# CAS_SMPS_Sheet.net
KiCad netlist of a schematic drawn in Altium Designer
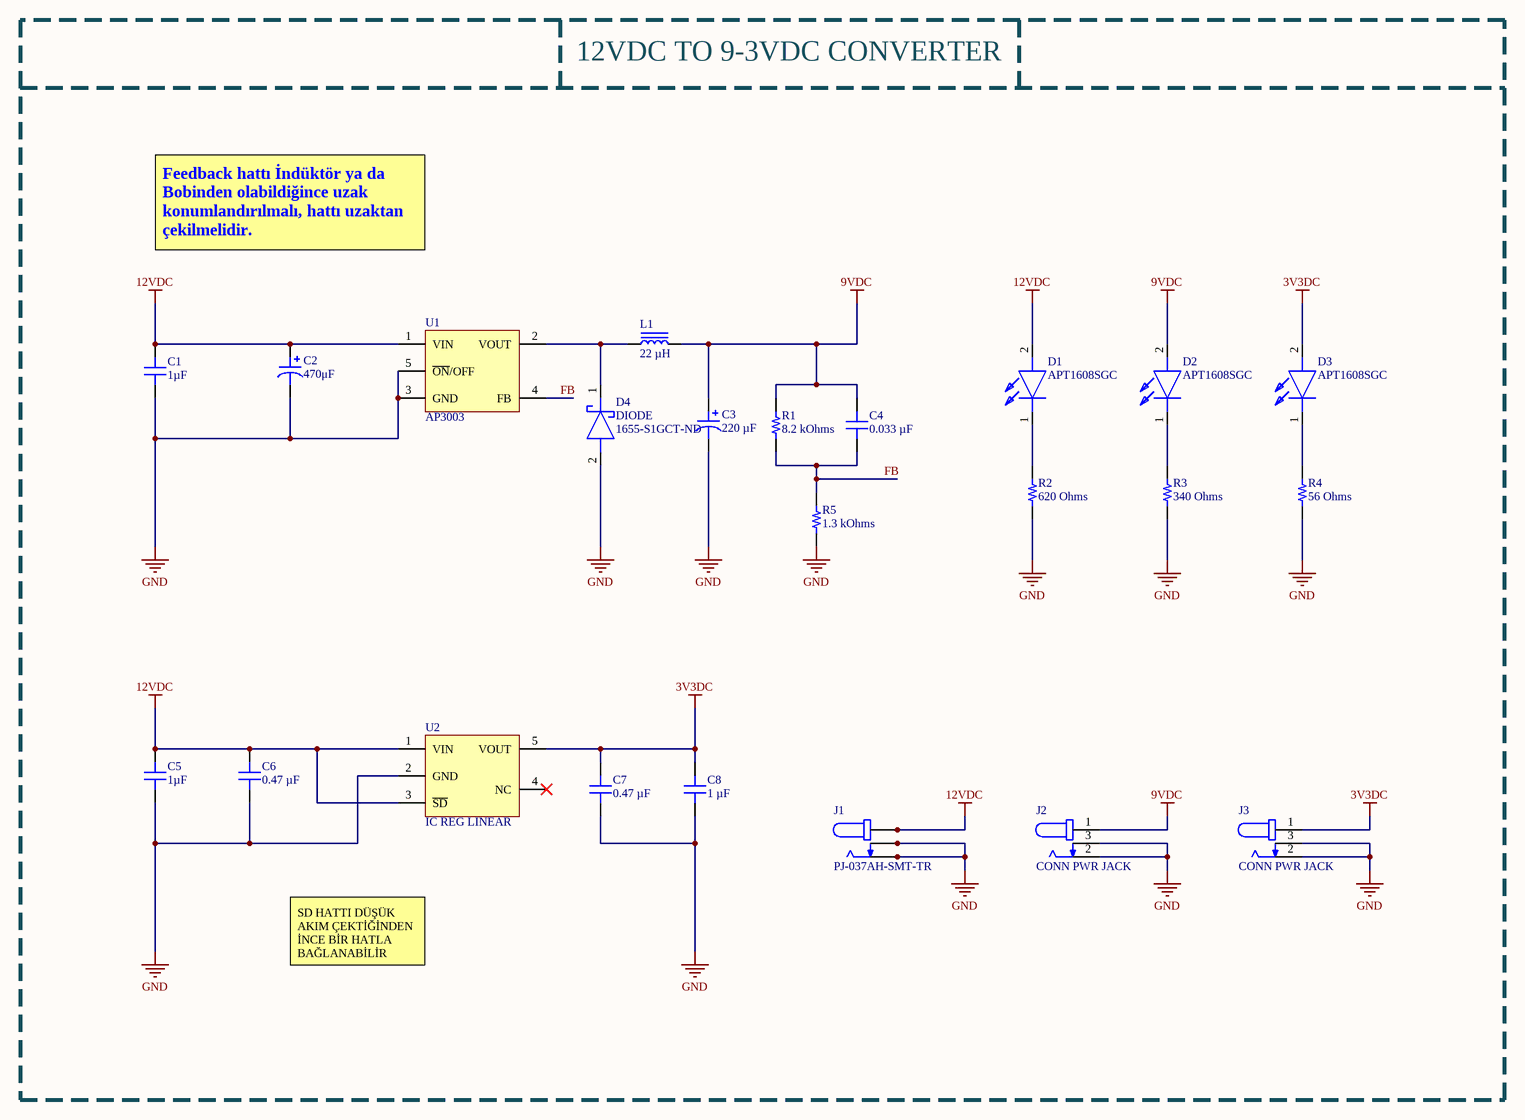
[diagram p0: CAS_SMPS_Sheet.SchDoc]

(export (version "E")
  (design (tool "Eeschema 10.0.6"))
  (components
    (comp (ref "C1")
      (value "1µF")
      (footprint "CAP 0603_1608")
      (description "CAP CER 1UF 25V X5R 0603")
      (fields (field (name "PART NUMBER") "06033D105MAT2A"))
      (libsource (lib "Celestial Altium Library - altium_library") (part "Capacitor"))
    )
    (comp (ref "C2")
      (value "470μF")
      (footprint "CAP ALSMD 8.3MM H10.5MM")
      (description "CAP ALUM 470UF 20% 25V SMD")
      (fields (field (name "PART NUMBER") "25TPV470M8X10.5"))
      (libsource (lib "Celestial Altium Library - altium_library") (part "Polarised Capacitor"))
    )
    (comp (ref "C3")
      (value "220 µF")
      (footprint "CAP ALSMD 8.3MM H10.5MM")
      (description "CAP ALUM 220UF 20% 25V SMD")
      (fields (field (name "PART NUMBER") "25TXV220M8X10.5") (field (name "MANUFACTURER") "Rubycon"))
      (libsource (lib "Celestial Altium Library - altium_library") (part "Polarised Capacitor"))
    )
    (comp (ref "C4")
      (value "0.033 µF")
      (footprint "CAP 0603_1608")
      (description "CAP CER 0603 33NF 16V X7R 5%")
      (fields (field (name "PART NUMBER") "C0603C333J4REC7411"))
      (libsource (lib "Celestial Altium Library - altium_library") (part "Capacitor"))
    )
    (comp (ref "C5")
      (value "1µF")
      (footprint "CAP 0603_1608")
      (description "CAP CER 1UF 25V X5R 0603")
      (fields (field (name "PART NUMBER") "06033D105MAT2A"))
      (libsource (lib "Celestial Altium Library - altium_library") (part "Capacitor"))
    )
    (comp (ref "C6")
      (value "0.47 µF")
      (footprint "CAP 0603_1608")
      (description "CAP CER 0.47UF 25V X5R 0603")
      (fields (field (name "PART NUMBER") "CC0603KRX5R8BB474"))
      (libsource (lib "Celestial Altium Library - altium_library") (part "Capacitor"))
    )
    (comp (ref "C7")
      (value "0.47 µF")
      (footprint "CAP 0603_1608")
      (description "CAP CER 0.47UF 25V X5R 0603")
      (fields (field (name "PART NUMBER") "CC0603KRX5R8BB474"))
      (libsource (lib "Celestial Altium Library - altium_library") (part "Capacitor"))
    )
    (comp (ref "C8")
      (value "1 µF")
      (footprint "CAP 0603_1608")
      (description "CAP CER 1UF 16V X7R 0603")
      (fields (field (name "PART NUMBER") "C0603C105K4RACAUTO"))
      (libsource (lib "Celestial Altium Library - altium_library") (part "Capacitor"))
    )
    (comp (ref "D1")
      (value "APT1608SGC")
      (footprint "LED")
      (description "LED GREEN CLEAR 0603 SMD")
      (fields (field (name "MANUFACTURER") "Kingbright"))
      (libsource (lib "Integrated_Library1") (part "APT1608SGC"))
    )
    (comp (ref "D2")
      (value "APT1608SGC")
      (footprint "LED")
      (description "LED GREEN CLEAR 0603 SMD")
      (fields (field (name "MANUFACTURER") "Kingbright"))
      (libsource (lib "Integrated_Library1") (part "APT1608SGC"))
    )
    (comp (ref "D3")
      (value "APT1608SGC")
      (footprint "LED")
      (description "LED GREEN CLEAR 0603 SMD")
      (fields (field (name "MANUFACTURER") "Kingbright"))
      (libsource (lib "Integrated_Library1") (part "APT1608SGC"))
    )
    (comp (ref "D4")
      (value "DIODE")
      (footprint "DIODE2")
      (fields
        (field (name "MANUFACTURER") "Sangdest Microelectronics")
        (field (name "MANUFACTURER PART NUMBER") "S1G")
        (field (name "SUPPLIER PART NUMBER 1") "1655-S1GCT-ND")
      )
      (libsource (lib "Integrated_Library1") (part "DIODE"))
    )
    (comp (ref "J1")
      (value "PJ-037AH-SMT-TR")
      (footprint "JACK1")
      (description "2.0 x 6.3 mm, 5.0 A, Horizontal, Surface Mount (SMT), Dc Power Jack Connector")
      (fields (field (name "MANUFACTURER") "CUI"))
      (libsource (lib "Integrated_Library1") (part "PJ-037AH-SMT-TR"))
    )
    (comp (ref "J2")
      (value "CONN PWR JACK")
      (footprint "JACK2")
      (description "Power Barrel Connector Jack 2.00mm ID (0.079")
      (fields (field (name "MANUFACTURER") "CUI") (field (name "MANUFACTURER PART NUMBER") "PJ-006A-SMT-TR"))
      (libsource (lib "Integrated_Library1") (part "PJ-006A-SMT-TR"))
    )
    (comp (ref "J3")
      (value "CONN PWR JACK")
      (footprint "JACK2")
      (description "Power Barrel Connector Jack 2.00mm ID (0.079")
      (fields (field (name "MANUFACTURER") "CUI") (field (name "MANUFACTURER PART NUMBER") "PJ-006A-SMT-TR"))
      (libsource (lib "Integrated_Library1") (part "PJ-006A-SMT-TR"))
    )
    (comp (ref "L1")
      (value "22 µH")
      (footprint "BOURNS SRR1280")
      (description "FIXED IND 22UH 4.3A 38.6MOHM SMD")
      (fields (field (name "PART NUMBER") "SRR1280-220M") (field (name "MANUFACTURER") "Bourns Inc."))
      (libsource (lib "Celestial Altium Library - altium_library") (part "Inductor"))
    )
    (comp (ref "R1")
      (value "8.2 kOhms")
      (footprint "RES 0603_1608")
      (description "RES SMD 8.2K OHM 0.1% 1/10W 0603")
      (fields (field (name "PART NUMBER") "RT0603BRB078K2L"))
      (libsource (lib "Celestial Altium Library - altium_library") (part "Resistor"))
    )
    (comp (ref "R2")
      (value "620 Ohms")
      (footprint "RES 0603_1608")
      (description "RES SMD 620 OHM 0.5% 1/10W 0603")
      (fields (field (name "PART NUMBER") "ERA-3AED621V"))
      (libsource (lib "Celestial Altium Library - altium_library") (part "Resistor"))
    )
    (comp (ref "R3")
      (value "340 Ohms")
      (footprint "RES 0603_1608")
      (description "RES 340 OHM 1% 1/10W 0603")
      (fields (field (name "PART NUMBER") "RC0603FR-07340RL"))
      (libsource (lib "Celestial Altium Library - altium_library") (part "Resistor"))
    )
    (comp (ref "R4")
      (value "56 Ohms")
      (footprint "RES 0603_1608")
      (description "RES 56 OHM 1% 1/4W 0603")
      (fields (field (name "PART NUMBER") "CRGP0603F56R"))
      (libsource (lib "Celestial Altium Library - altium_library") (part "Resistor"))
    )
    (comp (ref "R5")
      (value "1.3 kOhms")
      (footprint "RES 0603_1608")
      (description "RQ 0603 1K3 0.1% 10PPM 1K RL")
      (fields (field (name "PART NUMBER") "RQ73C1J1K3BTDF"))
      (libsource (lib "Celestial Altium Library - altium_library") (part "Resistor"))
    )
    (comp (ref "U1")
      (value "AP3003")
      (footprint "TO-263-5")
      (description "IC REG BUCK ADJ 3A TO263-5")
      (libsource (lib "Integrated_Library1") (part "AP3003"))
    )
    (comp (ref "U2")
      (value "IC REG LINEAR")
      (footprint "SOT-23-5")
      (description "LDO Regulator Pos 3.3V 0.1A 5-Pin SOT-23 T/R / IC REG LDO 3.3V 0.1A SOT23-5")
      (fields
        (field (name "MANUFACTURER") "Analog Devices")
        (field (name "MANUFACTURER PART NUMBER") "ADP3309ARTZ-3.3-R7")
      )
      (libsource (lib "Integrated_Library1") (part "ADP3309ARTZ-3.3-R7"))
    )
  )
  (nets
    (net (code "1") (name "/FB") (class "Default")
      (node (ref "C4") (pin "2") (pinfunction "2_2") (pintype "passive"))
      (node (ref "R1") (pin "1") (pinfunction "1_1") (pintype "passive"))
      (node (ref "R5") (pin "1") (pinfunction "1_1") (pintype "passive"))
      (node (ref "U1") (pin "4") (pinfunction "FB_4") (pintype "passive"))
    )
    (net (code "2") (name "3V3DC") (class "Default")
      (node (ref "C7") (pin "2") (pinfunction "2_2") (pintype "passive"))
      (node (ref "C8") (pin "2") (pinfunction "2_2") (pintype "passive"))
      (node (ref "D3") (pin "2") (pinfunction "A_2") (pintype "passive"))
      (node (ref "J3") (pin "1") (pinfunction "1_1") (pintype "passive"))
      (node (ref "U2") (pin "5") (pinfunction "VOUT_5") (pintype "passive"))
    )
    (net (code "3") (name "9VDC") (class "Default")
      (node (ref "C3") (pin "1") (pinfunction "1_1") (pintype "passive"))
      (node (ref "C4") (pin "1") (pinfunction "1_1") (pintype "passive"))
      (node (ref "D2") (pin "2") (pinfunction "A_2") (pintype "passive"))
      (node (ref "J2") (pin "1") (pinfunction "1_1") (pintype "passive"))
      (node (ref "L1") (pin "2") (pinfunction "2_2") (pintype "passive"))
      (node (ref "R1") (pin "2") (pinfunction "2_2") (pintype "passive"))
    )
    (net (code "4") (name "12VDC") (class "Default")
      (node (ref "C1") (pin "2") (pinfunction "2_2") (pintype "passive"))
      (node (ref "C2") (pin "1") (pinfunction "1_1") (pintype "passive"))
      (node (ref "C5") (pin "2") (pinfunction "2_2") (pintype "passive"))
      (node (ref "C6") (pin "2") (pinfunction "2_2") (pintype "passive"))
      (node (ref "D1") (pin "2") (pinfunction "A_2") (pintype "passive"))
      (node (ref "J1") (pin "1A") (pinfunction "1_1A") (pintype "passive"))
      (node (ref "J1") (pin "1B") (pinfunction "1_1B") (pintype "passive"))
      (node (ref "U1") (pin "1") (pinfunction "VIN_1") (pintype "passive"))
      (node (ref "U2") (pin "1") (pinfunction "VIN_1") (pintype "passive"))
      (node (ref "U2") (pin "3") (pinfunction "~{SD}_3") (pintype "passive"))
    )
    (net (code "5") (name "GND") (class "Default")
      (node (ref "C1") (pin "1") (pinfunction "1_1") (pintype "passive"))
      (node (ref "C2") (pin "2") (pinfunction "2_2") (pintype "passive"))
      (node (ref "C3") (pin "2") (pinfunction "2_2") (pintype "passive"))
      (node (ref "C5") (pin "1") (pinfunction "1_1") (pintype "passive"))
      (node (ref "C6") (pin "1") (pinfunction "1_1") (pintype "passive"))
      (node (ref "C7") (pin "1") (pinfunction "1_1") (pintype "passive"))
      (node (ref "C8") (pin "1") (pinfunction "1_1") (pintype "passive"))
      (node (ref "D4") (pin "2") (pinfunction "A_2") (pintype "passive"))
      (node (ref "J1") (pin "2A") (pinfunction "2_2A") (pintype "passive"))
      (node (ref "J1") (pin "2B") (pinfunction "2_2B") (pintype "passive"))
      (node (ref "J1") (pin "3A") (pinfunction "3_3A") (pintype "passive"))
      (node (ref "J1") (pin "3B") (pinfunction "3_3B") (pintype "passive"))
      (node (ref "J2") (pin "2") (pinfunction "2_2") (pintype "passive"))
      (node (ref "J2") (pin "3") (pinfunction "3_3") (pintype "passive"))
      (node (ref "J3") (pin "2") (pinfunction "2_2") (pintype "passive"))
      (node (ref "J3") (pin "3") (pinfunction "3_3") (pintype "passive"))
      (node (ref "R2") (pin "1") (pinfunction "1_1") (pintype "passive"))
      (node (ref "R3") (pin "1") (pinfunction "1_1") (pintype "passive"))
      (node (ref "R4") (pin "1") (pinfunction "1_1") (pintype "passive"))
      (node (ref "R5") (pin "2") (pinfunction "2_2") (pintype "passive"))
      (node (ref "U1") (pin "3") (pinfunction "GND_3") (pintype "passive"))
      (node (ref "U1") (pin "5") (pinfunction "~{ON}/OFF_5") (pintype "passive"))
      (node (ref "U2") (pin "2") (pinfunction "GND_2") (pintype "passive"))
    )
    (net (code "6") (name "Net-(D1-K)") (class "Default")
      (node (ref "D1") (pin "1") (pinfunction "K_1") (pintype "passive"))
      (node (ref "R2") (pin "2") (pinfunction "2_2") (pintype "passive"))
    )
    (net (code "7") (name "Net-(D2-K)") (class "Default")
      (node (ref "D2") (pin "1") (pinfunction "K_1") (pintype "passive"))
      (node (ref "R3") (pin "2") (pinfunction "2_2") (pintype "passive"))
    )
    (net (code "8") (name "Net-(D3-K)") (class "Default")
      (node (ref "D3") (pin "1") (pinfunction "K_1") (pintype "passive"))
      (node (ref "R4") (pin "2") (pinfunction "2_2") (pintype "passive"))
    )
    (net (code "9") (name "Net-(D4-K)") (class "Default")
      (node (ref "D4") (pin "1") (pinfunction "K_1") (pintype "passive"))
      (node (ref "L1") (pin "1") (pinfunction "1_1") (pintype "passive"))
      (node (ref "U1") (pin "2") (pinfunction "VOUT_2") (pintype "passive"))
    )
    (net (code "10") (name "unconnected-(U2-NC-Pad4)") (class "Default")
      (node (ref "U2") (pin "4") (pinfunction "NC_4") (pintype "passive+no_connect"))
    )
  )
)
